# USB.net
KiCad netlist of a schematic drawn in Altium Designer
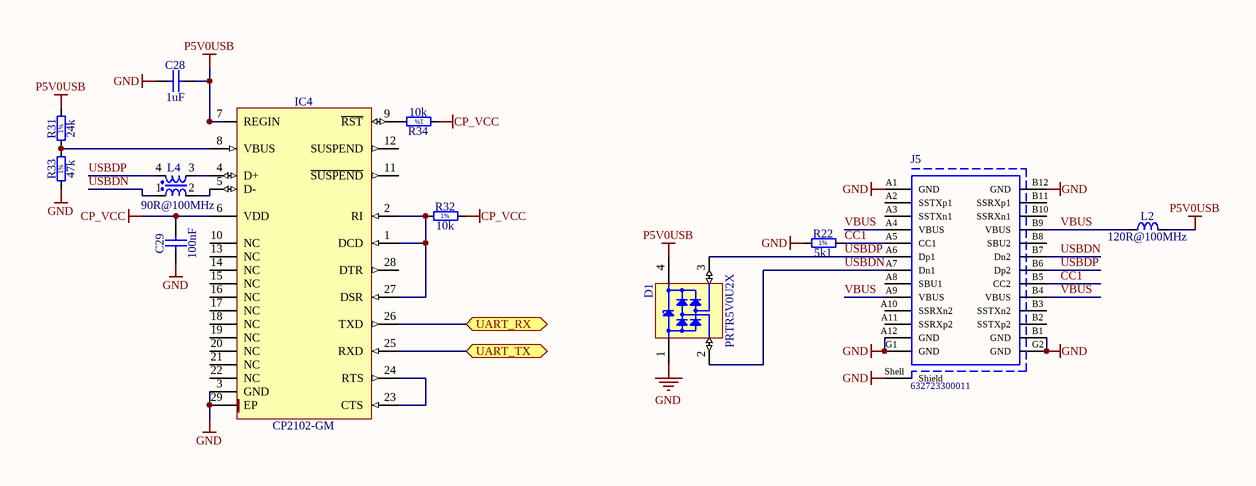
[diagram p0: USB.SchDoc]

(export (version "E")
  (design (tool "Eeschema 10.0.6"))
  (components
    (comp (ref "C28")
      (value "1uF")
      (footprint "CAPC1005X55N")
      (description "Non-polarised capacitor")
      (fields
        (field (name "PART NUMBER") "CC0402_1UF_16V_10%_X5R")
        (field (name "VOLTAGE") "16V")
        (field (name "AUTHOR") "CERN DEM JLC")
      )
      (libsource (lib "Capacitors") (part "Capacitor - non polarized"))
    )
    (comp (ref "C29")
      (value "100nF")
      (footprint "CAPC1005X55N")
      (description "Non-polarised capacitor")
      (fields
        (field (name "PART NUMBER") "CC0402_100NF_16V_10%_X5R")
        (field (name "VOLTAGE") "16V")
        (field (name "AUTHOR") "CERN DEM JLC")
      )
      (libsource (lib "Capacitors") (part "Capacitor - non polarized"))
    )
    (comp (ref "D1")
      (value "PRTR5V0U2X")
      (footprint "SOT190P230X110-4N")
      (description "Ultra Low Capacitance Double Rail-to-Rail ESD Protection Diode")
      (fields
        (field (name "VOLTAGE") "5.5V")
        (field (name "MANUFACTURER") "NXP SEMICONDUCTORS")
        (field (name "AUTHOR") "CERN DEM JLC")
      )
      (libsource (lib "ICs And Semiconductors") (part "PRTR5V0U2X"))
    )
    (comp (ref "IC4")
      (value "CP2102-GM")
      (footprint "QFN50P500X500X100-29N-S335")
      (description "Single-Chip USB to UART Bridge")
      (fields (field (name "MANUFACTURER") "SILICON LABS") (field (name "AUTHOR") "CERN DEM JLC"))
      (libsource (lib "ICs And Semiconductors") (part "CP2102-GM"))
    )
    (comp (ref "J5")
      (value "632723300011")
      (footprint "632723300011")
      (description "USB 3.1 Type C Receptacle WR-COM, Horizontal, SMT / THT")
      (fields (field (name "PUBLISHER") "Wurth Elektronik"))
      (libsource (lib "ALTIUM-WR-COM_USB_31-rev19a") (part "632723300011"))
    )
    (comp (ref "L2")
      (value "120R@100MHz")
      (footprint "INDC1608X65N")
      (description "Inductor")
      (fields
        (field (name "PART NUMBER") "IND0603_MURATA_BLM18SG121TN1D")
        (field (name "POWER") "3A")
        (field (name "AUTHOR") "CERN DEM JLC")
      )
      (libsource (lib "Inductors & Transformers") (part "Inductor"))
    )
    (comp (ref "L4")
      (value "90R@100MHz")
      (footprint "IND_MURATA_DLW21S")
      (description "Inductor Common Mode")
      (fields
        (field (name "PART NUMBER") "IND_MURATA_DLW21SN900SQ2L")
        (field (name "POWER") "330mA")
        (field (name "AUTHOR") "CERN DEM JLC")
      )
      (libsource (lib "Inductors & Transformers") (part "Inductor Common Mode 1Dot-2 4Dot-3"))
    )
    (comp (ref "R22")
      (value "5k1")
      (footprint "RESC1005X40N")
      (description "Resistor - 1%")
      (fields
        (field (name "PART NUMBER") "R0402_5K1_1%_0.0625W_100PPM")
        (field (name "POWER") "0.0625W")
        (field (name "AUTHOR") "CERN DEM JLC")
      )
      (libsource (lib "Resistors") (part "Resistor - 1%"))
    )
    (comp (ref "R31")
      (value "24k")
      (footprint "RESC1005X40N")
      (description "Resistor - 1%")
      (fields
        (field (name "PART NUMBER") "R0402_24K_1%_0.0625W_100PPM")
        (field (name "POWER") "0.0625W")
        (field (name "AUTHOR") "CERN DEM JLC")
      )
      (libsource (lib "Resistors") (part "Resistor - 1%"))
    )
    (comp (ref "R32")
      (value "10k")
      (footprint "RESC1005X40N")
      (description "Resistor - 1%")
      (fields
        (field (name "PART NUMBER") "R0402_10K_1%_0.0625W_100PPM")
        (field (name "POWER") "0.0625W")
        (field (name "AUTHOR") "CERN DEM JLC")
      )
      (libsource (lib "Resistors") (part "Resistor - 1%"))
    )
    (comp (ref "R33")
      (value "47k")
      (footprint "RESC1005X40N")
      (description "Resistor - 1%")
      (fields
        (field (name "PART NUMBER") "R0402_47K_1%_0.0625W_100PPM")
        (field (name "POWER") "0.0625W")
        (field (name "AUTHOR") "CERN DEM JLC")
      )
      (libsource (lib "Resistors") (part "Resistor - 1%"))
    )
    (comp (ref "R34")
      (value "10k")
      (footprint "RESC1005X40N")
      (description "Resistor - 1%")
      (fields
        (field (name "PART NUMBER") "R0402_10K_1%_0.0625W_100PPM")
        (field (name "POWER") "0.0625W")
        (field (name "AUTHOR") "CERN DEM JLC")
      )
      (libsource (lib "Resistors") (part "Resistor - 1%"))
    )
  )
  (nets
    (net (code "1") (name "/CC1") (class "Default")
      (node (ref "J5") (pin "A5") (pinfunction "CC1_A5") (pintype "passive"))
      (node (ref "J5") (pin "B5") (pinfunction "CC2_B5") (pintype "passive"))
      (node (ref "R22") (pin "2") (pinfunction "2_2") (pintype "passive"))
    )
    (net (code "2") (name "/UART_RX") (class "Default")
      (node (ref "IC4") (pin "26") (pinfunction "TXD_26") (pintype "output"))
    )
    (net (code "3") (name "/UART_TX") (class "Default")
      (node (ref "IC4") (pin "25") (pinfunction "RXD_25") (pintype "input"))
    )
    (net (code "4") (name "/USBDN") (class "Default")
      (node (ref "D1") (pin "2") (pinfunction "I/O1_2") (pintype "bidirectional"))
      (node (ref "J5") (pin "A7") (pinfunction "Dn1_A7") (pintype "passive"))
      (node (ref "J5") (pin "B7") (pinfunction "Dn2_B7") (pintype "passive"))
      (node (ref "L4") (pin "1") (pinfunction "1_1") (pintype "passive"))
    )
    (net (code "5") (name "/USBDP") (class "Default")
      (node (ref "D1") (pin "3") (pinfunction "I/O2_3") (pintype "bidirectional"))
      (node (ref "J5") (pin "A6") (pinfunction "Dp1_A6") (pintype "passive"))
      (node (ref "J5") (pin "B6") (pinfunction "Dp2_B6") (pintype "passive"))
      (node (ref "L4") (pin "4") (pinfunction "4_4") (pintype "passive"))
    )
    (net (code "6") (name "/VBUS") (class "Default")
      (node (ref "J5") (pin "A4") (pinfunction "VBUS_A4") (pintype "passive"))
      (node (ref "J5") (pin "A9") (pinfunction "VBUS_A9") (pintype "passive"))
      (node (ref "J5") (pin "B4") (pinfunction "VBUS_B4") (pintype "passive"))
      (node (ref "J5") (pin "B9") (pinfunction "VBUS_B9") (pintype "passive"))
      (node (ref "L2") (pin "1") (pinfunction "1_1") (pintype "passive"))
    )
    (net (code "7") (name "CP_VCC") (class "Default")
      (node (ref "C29") (pin "2") (pinfunction "2_2") (pintype "passive"))
      (node (ref "IC4") (pin "6") (pinfunction "VDD_6") (pintype "power_in"))
      (node (ref "R32") (pin "2") (pinfunction "2_2") (pintype "passive"))
      (node (ref "R34") (pin "1") (pinfunction "1_1") (pintype "passive"))
    )
    (net (code "8") (name "GND") (class "Default")
      (node (ref "C28") (pin "1") (pinfunction "1_1") (pintype "passive"))
      (node (ref "C29") (pin "1") (pinfunction "1_1") (pintype "passive"))
      (node (ref "D1") (pin "1") (pinfunction "GND_1") (pintype "power_in"))
      (node (ref "IC4") (pin "29") (pinfunction "EP_29") (pintype "power_in"))
      (node (ref "IC4") (pin "3") (pinfunction "GND_3") (pintype "power_in"))
      (node (ref "J5") (pin "A1") (pinfunction "GND_A1") (pintype "passive"))
      (node (ref "J5") (pin "A12") (pinfunction "GND_A12") (pintype "passive"))
      (node (ref "J5") (pin "B1") (pinfunction "GND_B1") (pintype "passive"))
      (node (ref "J5") (pin "B12") (pinfunction "GND_B12") (pintype "passive"))
      (node (ref "J5") (pin "G1") (pinfunction "GND_G1") (pintype "passive"))
      (node (ref "J5") (pin "G2") (pinfunction "GND_G2") (pintype "passive"))
      (node (ref "J5") (pin "Shell") (pinfunction "Shield_Shell") (pintype "passive"))
      (node (ref "R22") (pin "1") (pinfunction "1_1") (pintype "passive"))
      (node (ref "R33") (pin "1") (pinfunction "1_1") (pintype "passive"))
    )
    (net (code "9") (name "Net-(IC4-CTS)") (class "Default")
      (node (ref "IC4") (pin "23") (pinfunction "CTS_23") (pintype "input"))
      (node (ref "IC4") (pin "24") (pinfunction "RTS_24") (pintype "output"))
    )
    (net (code "10") (name "Net-(IC4-D+)") (class "Default")
      (node (ref "IC4") (pin "4") (pinfunction "D+_4") (pintype "bidirectional"))
      (node (ref "L4") (pin "3") (pinfunction "3_3") (pintype "passive"))
    )
    (net (code "11") (name "Net-(IC4-D-)") (class "Default")
      (node (ref "IC4") (pin "5") (pinfunction "D-_5") (pintype "bidirectional"))
      (node (ref "L4") (pin "2") (pinfunction "2_2") (pintype "passive"))
    )
    (net (code "12") (name "Net-(IC4-DCD)") (class "Default")
      (node (ref "IC4") (pin "1") (pinfunction "DCD_1") (pintype "input"))
      (node (ref "IC4") (pin "2") (pinfunction "RI_2") (pintype "input"))
      (node (ref "IC4") (pin "27") (pinfunction "DSR_27") (pintype "input"))
      (node (ref "R32") (pin "1") (pinfunction "1_1") (pintype "passive"))
    )
    (net (code "13") (name "Net-(IC4-VBUS)") (class "Default")
      (node (ref "IC4") (pin "8") (pinfunction "VBUS_8") (pintype "input"))
      (node (ref "R31") (pin "1") (pinfunction "1_1") (pintype "passive"))
      (node (ref "R33") (pin "2") (pinfunction "2_2") (pintype "passive"))
    )
    (net (code "14") (name "Net-(IC4-~{RST})") (class "Default")
      (node (ref "IC4") (pin "9") (pinfunction "~{RST}_9") (pintype "bidirectional"))
      (node (ref "R34") (pin "2") (pinfunction "2_2") (pintype "passive"))
    )
    (net (code "15") (name "P5V0USB") (class "Default")
      (node (ref "C28") (pin "2") (pinfunction "2_2") (pintype "passive"))
      (node (ref "D1") (pin "4") (pinfunction "VCC_4") (pintype "power_in"))
      (node (ref "IC4") (pin "7") (pinfunction "REGIN_7") (pintype "power_in"))
      (node (ref "L2") (pin "2") (pinfunction "2_2") (pintype "passive"))
      (node (ref "R31") (pin "2") (pinfunction "2_2") (pintype "passive"))
    )
    (net (code "16") (name "unconnected-(IC4-DTR-Pad28)") (class "Default")
      (node (ref "IC4") (pin "28") (pinfunction "DTR_28") (pintype "output"))
    )
    (net (code "17") (name "unconnected-(IC4-NC-Pad10)") (class "Default")
      (node (ref "IC4") (pin "10") (pinfunction "NC_10") (pintype "passive"))
    )
    (net (code "18") (name "unconnected-(IC4-NC-Pad13)") (class "Default")
      (node (ref "IC4") (pin "13") (pinfunction "NC_13") (pintype "passive"))
    )
    (net (code "19") (name "unconnected-(IC4-NC-Pad14)") (class "Default")
      (node (ref "IC4") (pin "14") (pinfunction "NC_14") (pintype "passive"))
    )
    (net (code "20") (name "unconnected-(IC4-NC-Pad15)") (class "Default")
      (node (ref "IC4") (pin "15") (pinfunction "NC_15") (pintype "passive"))
    )
    (net (code "21") (name "unconnected-(IC4-NC-Pad16)") (class "Default")
      (node (ref "IC4") (pin "16") (pinfunction "NC_16") (pintype "passive"))
    )
    (net (code "22") (name "unconnected-(IC4-NC-Pad17)") (class "Default")
      (node (ref "IC4") (pin "17") (pinfunction "NC_17") (pintype "passive"))
    )
    (net (code "23") (name "unconnected-(IC4-NC-Pad18)") (class "Default")
      (node (ref "IC4") (pin "18") (pinfunction "NC_18") (pintype "passive"))
    )
    (net (code "24") (name "unconnected-(IC4-NC-Pad19)") (class "Default")
      (node (ref "IC4") (pin "19") (pinfunction "NC_19") (pintype "passive"))
    )
    (net (code "25") (name "unconnected-(IC4-NC-Pad20)") (class "Default")
      (node (ref "IC4") (pin "20") (pinfunction "NC_20") (pintype "passive"))
    )
    (net (code "26") (name "unconnected-(IC4-NC-Pad21)") (class "Default")
      (node (ref "IC4") (pin "21") (pinfunction "NC_21") (pintype "passive"))
    )
    (net (code "27") (name "unconnected-(IC4-NC-Pad22)") (class "Default")
      (node (ref "IC4") (pin "22") (pinfunction "NC_22") (pintype "passive"))
    )
    (net (code "28") (name "unconnected-(IC4-SUSPEND-Pad12)") (class "Default")
      (node (ref "IC4") (pin "12") (pinfunction "SUSPEND_12") (pintype "output"))
    )
    (net (code "29") (name "unconnected-(IC4-~{SUSPEND}-Pad11)") (class "Default")
      (node (ref "IC4") (pin "11") (pinfunction "~{SUSPEND}_11") (pintype "output"))
    )
    (net (code "30") (name "unconnected-(J5-SBU1-PadA8)") (class "Default")
      (node (ref "J5") (pin "A8") (pinfunction "SBU1_A8") (pintype "passive"))
    )
    (net (code "31") (name "unconnected-(J5-SBU2-PadB8)") (class "Default")
      (node (ref "J5") (pin "B8") (pinfunction "SBU2_B8") (pintype "passive"))
    )
    (net (code "32") (name "unconnected-(J5-SSRXn1-PadB10)") (class "Default")
      (node (ref "J5") (pin "B10") (pinfunction "SSRXn1_B10") (pintype "passive"))
    )
    (net (code "33") (name "unconnected-(J5-SSRXn2-PadA10)") (class "Default")
      (node (ref "J5") (pin "A10") (pinfunction "SSRXn2_A10") (pintype "passive"))
    )
    (net (code "34") (name "unconnected-(J5-SSRXp1-PadB11)") (class "Default")
      (node (ref "J5") (pin "B11") (pinfunction "SSRXp1_B11") (pintype "passive"))
    )
    (net (code "35") (name "unconnected-(J5-SSRXp2-PadA11)") (class "Default")
      (node (ref "J5") (pin "A11") (pinfunction "SSRXp2_A11") (pintype "passive"))
    )
    (net (code "36") (name "unconnected-(J5-SSTXn1-PadA3)") (class "Default")
      (node (ref "J5") (pin "A3") (pinfunction "SSTXn1_A3") (pintype "passive"))
    )
    (net (code "37") (name "unconnected-(J5-SSTXn2-PadB3)") (class "Default")
      (node (ref "J5") (pin "B3") (pinfunction "SSTXn2_B3") (pintype "passive"))
    )
    (net (code "38") (name "unconnected-(J5-SSTXp1-PadA2)") (class "Default")
      (node (ref "J5") (pin "A2") (pinfunction "SSTXp1_A2") (pintype "passive"))
    )
    (net (code "39") (name "unconnected-(J5-SSTXp2-PadB2)") (class "Default")
      (node (ref "J5") (pin "B2") (pinfunction "SSTXp2_B2") (pintype "passive"))
    )
  )
)
